# wificontrolpanel.net
KiCad netlist of a schematic drawn in EAGLE
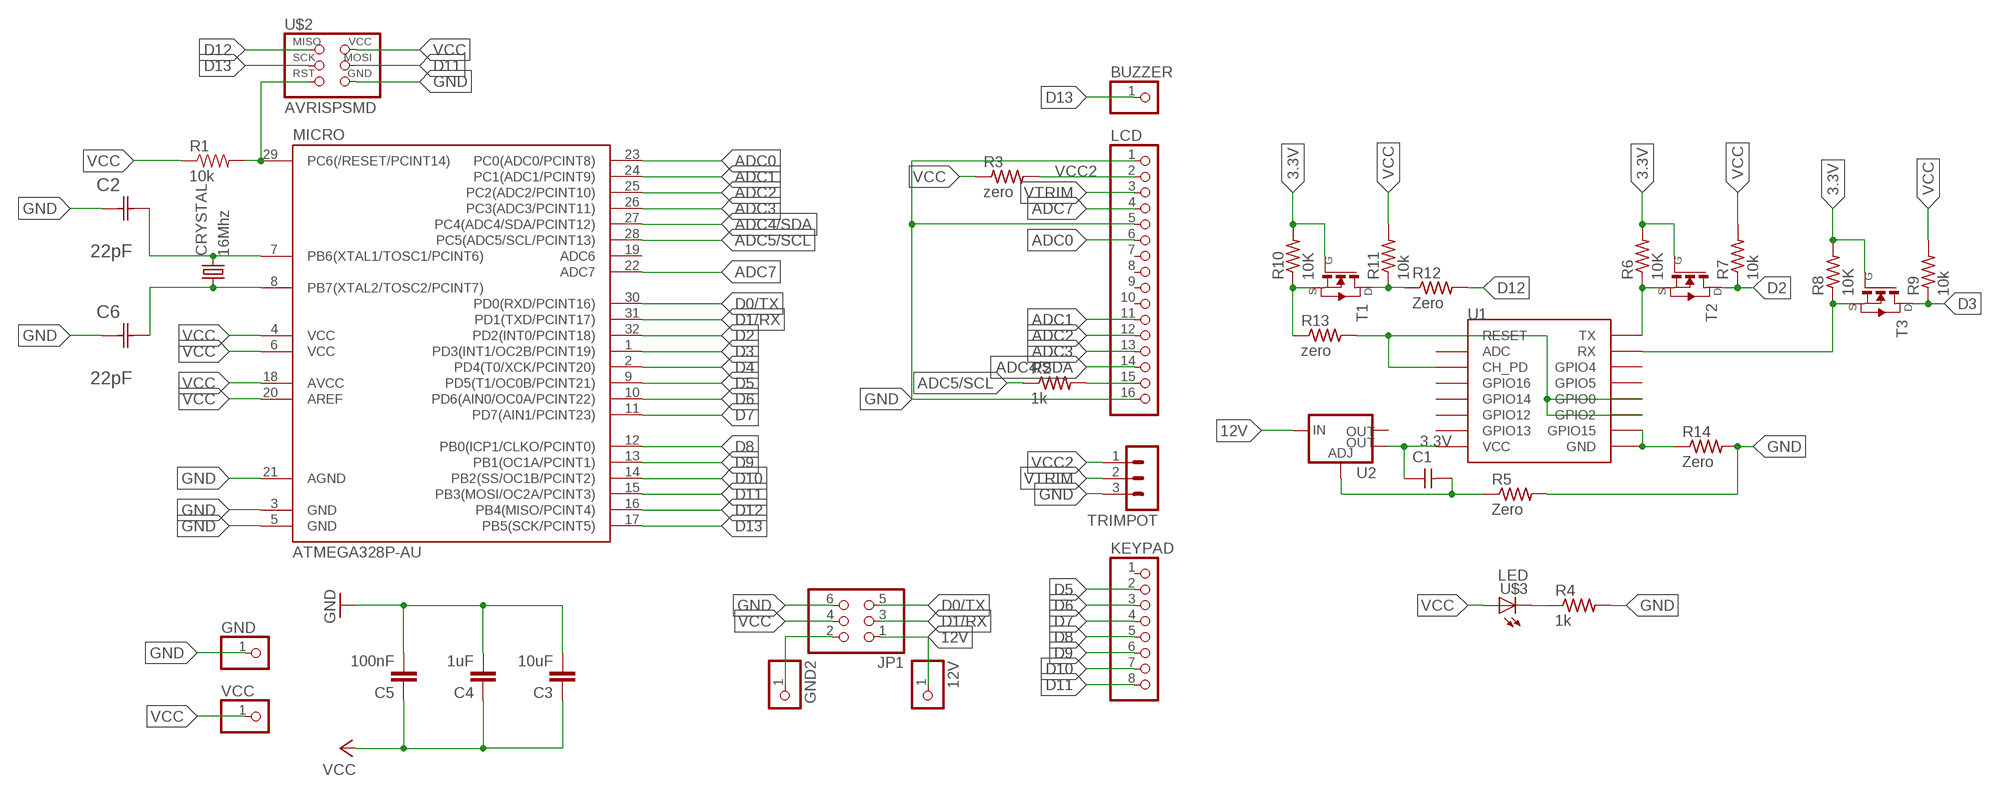
[diagram p0: schematic, sheet 1]

(export (version "E")
  (design (tool "Eeschema 10.0.6"))
  (components
    (comp (ref "12V")
      (value "PINHD-1X1")
      (footprint "eagle-import:1X01")
      (libsource (lib "eagle-import") (part "PINHD-1X1"))
    )
    (comp (ref "BUZZER")
      (value "PINHD-1X1")
      (footprint "eagle-import:1X01")
      (libsource (lib "eagle-import") (part "PINHD-1X1"))
    )
    (comp (ref "C1")
      (value "CAP-UNPOLARIZEDFAB")
      (footprint "eagle-import:C1206FAB")
      (libsource (lib "eagle-import") (part "CAP-UNPOLARIZEDFAB"))
    )
    (comp (ref "C2")
      (value "22pF")
      (footprint "eagle-import:CAPC3216X178N")
      (fields (field (name "MPN") "0612ZC225MAT2A") (field (name "TOLERANCE") "±20%"))
      (libsource (lib "eagle-import") (part "0612ZC225MAT2A"))
    )
    (comp (ref "C3")
      (value "10uF")
      (footprint "eagle-import:1206")
      (libsource (lib "eagle-import") (part "CAP1206"))
    )
    (comp (ref "C4")
      (value "1uF")
      (footprint "eagle-import:1206")
      (libsource (lib "eagle-import") (part "CAP1206"))
    )
    (comp (ref "C5")
      (value "100nF")
      (footprint "eagle-import:1206")
      (libsource (lib "eagle-import") (part "CAP1206"))
    )
    (comp (ref "C6")
      (value "22pF")
      (footprint "eagle-import:CAPC3216X178N")
      (fields (field (name "MPN") "0612ZC225MAT2A") (field (name "TOLERANCE") "±20%"))
      (libsource (lib "eagle-import") (part "0612ZC225MAT2A"))
    )
    (comp (ref "CRYSTAL")
      (value "16Mhz")
      (footprint "eagle-import:CSM-7X-DU")
      (libsource (lib "eagle-import") (part "CSM-7X-DU"))
    )
    (comp (ref "GND")
      (value "PINHD-1X1")
      (footprint "eagle-import:1X01")
      (libsource (lib "eagle-import") (part "PINHD-1X1"))
    )
    (comp (ref "GND2")
      (value "PINHD-1X1")
      (footprint "eagle-import:1X01")
      (libsource (lib "eagle-import") (part "PINHD-1X1"))
    )
    (comp (ref "JP1")
      (value "PINHD-2X3-SMD")
      (footprint "eagle-import:2X03SMD")
      (libsource (lib "eagle-import") (part "PINHD-2X3-SMD"))
    )
    (comp (ref "KEYPAD")
      (value "PINHD-1X8")
      (footprint "eagle-import:1X08")
      (libsource (lib "eagle-import") (part "PINHD-1X8"))
    )
    (comp (ref "LCD")
      (value "PINHD-1X16")
      (footprint "eagle-import:1X16")
      (libsource (lib "eagle-import") (part "PINHD-1X16"))
    )
    (comp (ref "MICRO")
      (value "ATMEGA328P-AU")
      (footprint "eagle-import:TQFP32-08")
      (libsource (lib "eagle-import") (part "ATMEGA48/88/168-AU"))
    )
    (comp (ref "R1")
      (value "10k")
      (footprint "eagle-import:1206")
      (libsource (lib "eagle-import") (part "RESISTOR1206"))
    )
    (comp (ref "R2")
      (value "1k")
      (footprint "eagle-import:R1206FAB")
      (libsource (lib "eagle-import") (part "RES-US1206FAB"))
    )
    (comp (ref "R3")
      (value "zero")
      (footprint "eagle-import:R1206FAB")
      (libsource (lib "eagle-import") (part "RES-US1206FAB"))
    )
    (comp (ref "R4")
      (value "1k")
      (footprint "eagle-import:R1206")
      (libsource (lib "eagle-import") (part "RES-US1206"))
    )
    (comp (ref "R5")
      (value "Zero")
      (footprint "eagle-import:R1206FAB")
      (libsource (lib "eagle-import") (part "RES-US1206FAB"))
    )
    (comp (ref "R6")
      (value "10K")
      (footprint "eagle-import:R1206FAB")
      (libsource (lib "eagle-import") (part "RES-US1206FAB"))
    )
    (comp (ref "R7")
      (value "10k")
      (footprint "eagle-import:R1206FAB")
      (libsource (lib "eagle-import") (part "RES-US1206FAB"))
    )
    (comp (ref "R8")
      (value "10K")
      (footprint "eagle-import:R1206FAB")
      (libsource (lib "eagle-import") (part "RES-US1206FAB"))
    )
    (comp (ref "R9")
      (value "10k")
      (footprint "eagle-import:R1206FAB")
      (libsource (lib "eagle-import") (part "RES-US1206FAB"))
    )
    (comp (ref "R10")
      (value "10K")
      (footprint "eagle-import:R1206FAB")
      (libsource (lib "eagle-import") (part "RES-US1206FAB"))
    )
    (comp (ref "R11")
      (value "10k")
      (footprint "eagle-import:R1206FAB")
      (libsource (lib "eagle-import") (part "RES-US1206FAB"))
    )
    (comp (ref "R12")
      (value "Zero")
      (footprint "eagle-import:R1206FAB")
      (libsource (lib "eagle-import") (part "RES-US1206FAB"))
    )
    (comp (ref "R13")
      (value "zero")
      (footprint "eagle-import:R1206FAB")
      (libsource (lib "eagle-import") (part "RES-US1206FAB"))
    )
    (comp (ref "R14")
      (value "Zero")
      (footprint "eagle-import:R1206FAB")
      (libsource (lib "eagle-import") (part "RES-US1206FAB"))
    )
    (comp (ref "T1")
      (value "NMOSFETSOT23")
      (footprint "eagle-import:SOT-23")
      (libsource (lib "eagle-import") (part "NMOSFETSOT23"))
    )
    (comp (ref "T2")
      (value "NMOSFETSOT23")
      (footprint "eagle-import:SOT-23")
      (libsource (lib "eagle-import") (part "NMOSFETSOT23"))
    )
    (comp (ref "T3")
      (value "NMOSFETSOT23")
      (footprint "eagle-import:SOT-23")
      (libsource (lib "eagle-import") (part "NMOSFETSOT23"))
    )
    (comp (ref "TRIMPOT")
      (value "MA03-1")
      (footprint "eagle-import:MA03-1")
      (libsource (lib "eagle-import") (part "MA03-1"))
    )
    (comp (ref "U$2")
      (value "AVRISPSMD")
      (footprint "eagle-import:2X03SMD")
      (libsource (lib "eagle-import") (part "AVRISPSMD"))
    )
    (comp (ref "U$3")
      (value "LED")
      (footprint "eagle-import:LED1206")
      (libsource (lib "eagle-import") (part "LED"))
    )
    (comp (ref "U1")
      (value "ESP12SMD")
      (footprint "eagle-import:ESP12-SMD")
      (libsource (lib "eagle-import") (part "ESP12SMD"))
    )
    (comp (ref "U2")
      (value "V_REG_LM1117SOT223")
      (footprint "eagle-import:SOT223")
      (libsource (lib "eagle-import") (part "V_REG_LM1117SOT223"))
    )
    (comp (ref "VCC")
      (value "PINHD-1X1")
      (footprint "eagle-import:1X01")
      (libsource (lib "eagle-import") (part "PINHD-1X1"))
    )
  )
  (nets
    (net (code "1") (name "3.3V") (class "Default")
      (node (ref "C1") (pin "1") (pinfunction "1_1") (pintype "passive"))
      (node (ref "R10") (pin "2") (pinfunction "2_2") (pintype "passive"))
      (node (ref "R6") (pin "2") (pinfunction "2_2") (pintype "passive"))
      (node (ref "R8") (pin "2") (pinfunction "2_2") (pintype "passive"))
      (node (ref "T1") (pin "3") (pinfunction "G_3") (pintype "passive"))
      (node (ref "T2") (pin "3") (pinfunction "G_3") (pintype "passive"))
      (node (ref "T3") (pin "3") (pinfunction "G_3") (pintype "passive"))
      (node (ref "U1") (pin "VCC") (pinfunction "VCC_VCC") (pintype "bidirectional"))
      (node (ref "U2") (pin "4") (pinfunction "OUT_4") (pintype "output"))
    )
    (net (code "2") (name "12V") (class "Default")
      (node (ref "12V") (pin "1") (pinfunction "1_1") (pintype "passive"))
      (node (ref "JP1") (pin "1") (pinfunction "1_1") (pintype "passive"))
      (node (ref "U2") (pin "3") (pinfunction "IN_3") (pintype "input"))
    )
    (net (code "3") (name "ADC0") (class "Default")
      (node (ref "LCD") (pin "6") (pinfunction "6_6") (pintype "passive"))
      (node (ref "MICRO") (pin "23") (pinfunction "PC0(ADC0/PCINT8)_23") (pintype "bidirectional"))
    )
    (net (code "4") (name "ADC1") (class "Default")
      (node (ref "LCD") (pin "11") (pinfunction "11_11") (pintype "passive"))
      (node (ref "MICRO") (pin "24") (pinfunction "PC1(ADC1/PCINT9)_24") (pintype "bidirectional"))
    )
    (net (code "5") (name "ADC2") (class "Default")
      (node (ref "LCD") (pin "12") (pinfunction "12_12") (pintype "passive"))
      (node (ref "MICRO") (pin "25") (pinfunction "PC2(ADC2/PCINT10)_25") (pintype "bidirectional"))
    )
    (net (code "6") (name "ADC3") (class "Default")
      (node (ref "LCD") (pin "13") (pinfunction "13_13") (pintype "passive"))
      (node (ref "MICRO") (pin "26") (pinfunction "PC3(ADC3/PCINT11)_26") (pintype "bidirectional"))
    )
    (net (code "7") (name "ADC4{slash}SDA") (class "Default")
      (node (ref "LCD") (pin "14") (pinfunction "14_14") (pintype "passive"))
      (node (ref "MICRO") (pin "27") (pinfunction "PC4(ADC4/SDA/PCINT12)_27") (pintype "bidirectional"))
    )
    (net (code "8") (name "ADC5{slash}SCL") (class "Default")
      (node (ref "MICRO") (pin "28") (pinfunction "PC5(ADC5/SCL/PCINT13)_28") (pintype "bidirectional"))
      (node (ref "R2") (pin "1") (pinfunction "1_1") (pintype "passive"))
    )
    (net (code "9") (name "ADC7") (class "Default")
      (node (ref "LCD") (pin "4") (pinfunction "4_4") (pintype "passive"))
      (node (ref "MICRO") (pin "22") (pinfunction "ADC7_22") (pintype "passive"))
    )
    (net (code "10") (name "D0{slash}TX") (class "Default")
      (node (ref "JP1") (pin "5") (pinfunction "5_5") (pintype "passive"))
      (node (ref "MICRO") (pin "30") (pinfunction "PD0(RXD/PCINT16)_30") (pintype "bidirectional"))
    )
    (net (code "11") (name "D1{slash}RX") (class "Default")
      (node (ref "JP1") (pin "3") (pinfunction "3_3") (pintype "passive"))
      (node (ref "MICRO") (pin "31") (pinfunction "PD1(TXD/PCINT17)_31") (pintype "bidirectional"))
    )
    (net (code "12") (name "D2") (class "Default")
      (node (ref "MICRO") (pin "32") (pinfunction "PD2(INT0/PCINT18)_32") (pintype "bidirectional"))
      (node (ref "R7") (pin "1") (pinfunction "1_1") (pintype "passive"))
      (node (ref "T2") (pin "1") (pinfunction "D_1") (pintype "passive"))
    )
    (net (code "13") (name "D3") (class "Default")
      (node (ref "MICRO") (pin "1") (pinfunction "PD3(INT1/OC2B/PCINT19)_1") (pintype "bidirectional"))
      (node (ref "R9") (pin "1") (pinfunction "1_1") (pintype "passive"))
      (node (ref "T3") (pin "1") (pinfunction "D_1") (pintype "passive"))
    )
    (net (code "14") (name "D4") (class "Default")
      (node (ref "MICRO") (pin "2") (pinfunction "PD4(T0/XCK/PCINT20)_2") (pintype "bidirectional"))
    )
    (net (code "15") (name "D5") (class "Default")
      (node (ref "KEYPAD") (pin "2") (pinfunction "2_2") (pintype "passive"))
      (node (ref "MICRO") (pin "9") (pinfunction "PD5(T1/OC0B/PCINT21)_9") (pintype "bidirectional"))
    )
    (net (code "16") (name "D6") (class "Default")
      (node (ref "KEYPAD") (pin "3") (pinfunction "3_3") (pintype "passive"))
      (node (ref "MICRO") (pin "10") (pinfunction "PD6(AIN0/OC0A/PCINT22)_10") (pintype "bidirectional"))
    )
    (net (code "17") (name "D7") (class "Default")
      (node (ref "KEYPAD") (pin "4") (pinfunction "4_4") (pintype "passive"))
      (node (ref "MICRO") (pin "11") (pinfunction "PD7(AIN1/PCINT23)_11") (pintype "bidirectional"))
    )
    (net (code "18") (name "D8") (class "Default")
      (node (ref "KEYPAD") (pin "5") (pinfunction "5_5") (pintype "passive"))
      (node (ref "MICRO") (pin "12") (pinfunction "PB0(ICP1/CLKO/PCINT0)_12") (pintype "bidirectional"))
    )
    (net (code "19") (name "D9") (class "Default")
      (node (ref "KEYPAD") (pin "6") (pinfunction "6_6") (pintype "passive"))
      (node (ref "MICRO") (pin "13") (pinfunction "PB1(OC1A/PCINT1)_13") (pintype "bidirectional"))
    )
    (net (code "20") (name "D10") (class "Default")
      (node (ref "KEYPAD") (pin "7") (pinfunction "7_7") (pintype "passive"))
      (node (ref "MICRO") (pin "14") (pinfunction "PB2(SS/OC1B/PCINT2)_14") (pintype "bidirectional"))
    )
    (net (code "21") (name "D11") (class "Default")
      (node (ref "KEYPAD") (pin "8") (pinfunction "8_8") (pintype "passive"))
      (node (ref "MICRO") (pin "15") (pinfunction "PB3(MOSI/OC2A/PCINT3)_15") (pintype "bidirectional"))
      (node (ref "U$2") (pin "4") (pinfunction "MOSI_4") (pintype "passive"))
    )
    (net (code "22") (name "D12") (class "Default")
      (node (ref "MICRO") (pin "16") (pinfunction "PB4(MISO/PCINT4)_16") (pintype "bidirectional"))
      (node (ref "R12") (pin "2") (pinfunction "2_2") (pintype "passive"))
      (node (ref "U$2") (pin "1") (pinfunction "MISO_1") (pintype "passive"))
    )
    (net (code "23") (name "D13") (class "Default")
      (node (ref "BUZZER") (pin "1") (pinfunction "1_1") (pintype "passive"))
      (node (ref "MICRO") (pin "17") (pinfunction "PB5(SCK/PCINT5)_17") (pintype "bidirectional"))
      (node (ref "U$2") (pin "3") (pinfunction "SCK_3") (pintype "passive"))
    )
    (net (code "24") (name "GND") (class "Default")
      (node (ref "C2") (pin "1") (pinfunction "C1_1") (pintype "passive"))
      (node (ref "C3") (pin "2") (pinfunction "2_2") (pintype "passive"))
      (node (ref "C4") (pin "2") (pinfunction "2_2") (pintype "passive"))
      (node (ref "C5") (pin "2") (pinfunction "2_2") (pintype "passive"))
      (node (ref "C6") (pin "1") (pinfunction "C1_1") (pintype "passive"))
      (node (ref "GND") (pin "1") (pinfunction "1_1") (pintype "passive"))
      (node (ref "JP1") (pin "6") (pinfunction "6_6") (pintype "passive"))
      (node (ref "LCD") (pin "1") (pinfunction "1_1") (pintype "passive"))
      (node (ref "LCD") (pin "16") (pinfunction "16_16") (pintype "passive"))
      (node (ref "LCD") (pin "5") (pinfunction "5_5") (pintype "passive"))
      (node (ref "MICRO") (pin "21") (pinfunction "AGND_21") (pintype "power_in"))
      (node (ref "MICRO") (pin "3") (pinfunction "GND_3") (pintype "power_in"))
      (node (ref "MICRO") (pin "5") (pinfunction "GND_5") (pintype "power_in"))
      (node (ref "R14") (pin "2") (pinfunction "2_2") (pintype "passive"))
      (node (ref "R4") (pin "2") (pinfunction "2_2") (pintype "passive"))
      (node (ref "R5") (pin "2") (pinfunction "2_2") (pintype "passive"))
      (node (ref "TRIMPOT") (pin "3") (pinfunction "3_3") (pintype "passive"))
      (node (ref "U$2") (pin "6") (pinfunction "GND_6") (pintype "passive"))
    )
    (net (code "25") (name "Net-(C2-C2)") (class "Default")
      (node (ref "C2") (pin "2") (pinfunction "C2_2") (pintype "passive"))
      (node (ref "CRYSTAL") (pin "2") (pinfunction "2_2") (pintype "passive"))
      (node (ref "MICRO") (pin "7") (pinfunction "PB6(XTAL1/TOSC1/PCINT6)_7") (pintype "bidirectional"))
    )
    (net (code "26") (name "Net-(C6-C2)") (class "Default")
      (node (ref "C6") (pin "2") (pinfunction "C2_2") (pintype "passive"))
      (node (ref "CRYSTAL") (pin "1") (pinfunction "1_1") (pintype "passive"))
      (node (ref "MICRO") (pin "8") (pinfunction "PB7(XTAL2/TOSC2/PCINT7)_8") (pintype "bidirectional"))
    )
    (net (code "27") (name "Net-(GND2-Pad1)") (class "Default")
      (node (ref "GND2") (pin "1") (pinfunction "1_1") (pintype "passive"))
      (node (ref "JP1") (pin "2") (pinfunction "2_2") (pintype "passive"))
    )
    (net (code "28") (name "Net-(LCD-Pad15)") (class "Default")
      (node (ref "LCD") (pin "15") (pinfunction "15_15") (pintype "passive"))
      (node (ref "R2") (pin "2") (pinfunction "2_2") (pintype "passive"))
    )
    (net (code "29") (name "Net-(MICRO-PC6({slash}RESET{slash}PCINT14))") (class "Default")
      (node (ref "MICRO") (pin "29") (pinfunction "PC6(/RESET/PCINT14)_29") (pintype "bidirectional"))
      (node (ref "R1") (pin "2") (pinfunction "2_2") (pintype "passive"))
      (node (ref "U$2") (pin "5") (pinfunction "RST_5") (pintype "passive"))
    )
    (net (code "30") (name "Net-(R13-Pad2)") (class "Default")
      (node (ref "R13") (pin "2") (pinfunction "2_2") (pintype "passive"))
      (node (ref "U1") (pin "CH_PD") (pinfunction "CH_PD_CH_PD") (pintype "bidirectional"))
      (node (ref "U1") (pin "GPIO0") (pinfunction "GPIO0_GPIO0") (pintype "bidirectional"))
      (node (ref "U1") (pin "GPIO2") (pinfunction "GPIO2_GPIO2") (pintype "bidirectional"))
      (node (ref "U1") (pin "RESET") (pinfunction "RESET_RESET") (pintype "bidirectional"))
    )
    (net (code "31") (name "Net-(R14-Pad1)") (class "Default")
      (node (ref "R14") (pin "1") (pinfunction "1_1") (pintype "passive"))
      (node (ref "U1") (pin "GND") (pinfunction "GND_GND") (pintype "bidirectional"))
      (node (ref "U1") (pin "GPIO15") (pinfunction "GPIO15_GPIO15") (pintype "bidirectional"))
    )
    (net (code "32") (name "Net-(T1-D)") (class "Default")
      (node (ref "R11") (pin "1") (pinfunction "1_1") (pintype "passive"))
      (node (ref "R12") (pin "1") (pinfunction "1_1") (pintype "passive"))
      (node (ref "T1") (pin "1") (pinfunction "D_1") (pintype "passive"))
    )
    (net (code "33") (name "Net-(T1-S)") (class "Default")
      (node (ref "R10") (pin "1") (pinfunction "1_1") (pintype "passive"))
      (node (ref "R13") (pin "1") (pinfunction "1_1") (pintype "passive"))
      (node (ref "T1") (pin "2") (pinfunction "S_2") (pintype "passive"))
    )
    (net (code "34") (name "Net-(T2-S)") (class "Default")
      (node (ref "R6") (pin "1") (pinfunction "1_1") (pintype "passive"))
      (node (ref "T2") (pin "2") (pinfunction "S_2") (pintype "passive"))
      (node (ref "U1") (pin "TXD0") (pinfunction "TX_TXD0") (pintype "bidirectional"))
    )
    (net (code "35") (name "Net-(T3-S)") (class "Default")
      (node (ref "R8") (pin "1") (pinfunction "1_1") (pintype "passive"))
      (node (ref "T3") (pin "2") (pinfunction "S_2") (pintype "passive"))
      (node (ref "U1") (pin "RXD0") (pinfunction "RX_RXD0") (pintype "bidirectional"))
    )
    (net (code "36") (name "Net-(U$3-C)") (class "Default")
      (node (ref "R4") (pin "1") (pinfunction "1_1") (pintype "passive"))
      (node (ref "U$3") (pin "2") (pinfunction "C_2") (pintype "passive"))
    )
    (net (code "37") (name "Net-(U2-ADJ)") (class "Default")
      (node (ref "C1") (pin "2") (pinfunction "2_2") (pintype "passive"))
      (node (ref "R5") (pin "1") (pinfunction "1_1") (pintype "passive"))
      (node (ref "U2") (pin "1") (pinfunction "ADJ_1") (pintype "input"))
    )
    (net (code "38") (name "VCC") (class "Default")
      (node (ref "C3") (pin "1") (pinfunction "1_1") (pintype "passive"))
      (node (ref "C4") (pin "1") (pinfunction "1_1") (pintype "passive"))
      (node (ref "C5") (pin "1") (pinfunction "1_1") (pintype "passive"))
      (node (ref "JP1") (pin "4") (pinfunction "4_4") (pintype "passive"))
      (node (ref "MICRO") (pin "18") (pinfunction "AVCC_18") (pintype "passive"))
      (node (ref "MICRO") (pin "20") (pinfunction "AREF_20") (pintype "passive"))
      (node (ref "MICRO") (pin "4") (pinfunction "VCC_4") (pintype "power_in"))
      (node (ref "MICRO") (pin "6") (pinfunction "VCC_6") (pintype "power_in"))
      (node (ref "R1") (pin "1") (pinfunction "1_1") (pintype "passive"))
      (node (ref "R11") (pin "2") (pinfunction "2_2") (pintype "passive"))
      (node (ref "R3") (pin "1") (pinfunction "1_1") (pintype "passive"))
      (node (ref "R7") (pin "2") (pinfunction "2_2") (pintype "passive"))
      (node (ref "R9") (pin "2") (pinfunction "2_2") (pintype "passive"))
      (node (ref "U$2") (pin "2") (pinfunction "VCC_2") (pintype "passive"))
      (node (ref "U$3") (pin "1") (pinfunction "A_1") (pintype "passive"))
      (node (ref "VCC") (pin "1") (pinfunction "1_1") (pintype "passive"))
    )
    (net (code "39") (name "VCC2") (class "Default")
      (node (ref "LCD") (pin "2") (pinfunction "2_2") (pintype "passive"))
      (node (ref "R3") (pin "2") (pinfunction "2_2") (pintype "passive"))
      (node (ref "TRIMPOT") (pin "1") (pinfunction "1_1") (pintype "passive"))
    )
    (net (code "40") (name "VTRIM") (class "Default")
      (node (ref "LCD") (pin "3") (pinfunction "3_3") (pintype "passive"))
      (node (ref "TRIMPOT") (pin "2") (pinfunction "2_2") (pintype "passive"))
    )
    (net (code "41") (name "unconnected-(KEYPAD-Pad1)") (class "Default")
      (node (ref "KEYPAD") (pin "1") (pinfunction "1_1") (pintype "passive"))
    )
    (net (code "42") (name "unconnected-(LCD-Pad7)") (class "Default")
      (node (ref "LCD") (pin "7") (pinfunction "7_7") (pintype "passive"))
    )
    (net (code "43") (name "unconnected-(LCD-Pad8)") (class "Default")
      (node (ref "LCD") (pin "8") (pinfunction "8_8") (pintype "passive"))
    )
    (net (code "44") (name "unconnected-(LCD-Pad9)") (class "Default")
      (node (ref "LCD") (pin "9") (pinfunction "9_9") (pintype "passive"))
    )
    (net (code "45") (name "unconnected-(LCD-Pad10)") (class "Default")
      (node (ref "LCD") (pin "10") (pinfunction "10_10") (pintype "passive"))
    )
    (net (code "46") (name "unconnected-(MICRO-ADC6-Pad19)") (class "Default")
      (node (ref "MICRO") (pin "19") (pinfunction "ADC6_19") (pintype "passive"))
    )
    (net (code "47") (name "unconnected-(U1-PadADC)") (class "Default")
      (node (ref "U1") (pin "ADC") (pinfunction "ADC_ADC") (pintype "bidirectional"))
    )
    (net (code "48") (name "unconnected-(U1-PadGPIO4)") (class "Default")
      (node (ref "U1") (pin "GPIO4") (pinfunction "GPIO4_GPIO4") (pintype "bidirectional"))
    )
    (net (code "49") (name "unconnected-(U1-PadGPIO5)") (class "Default")
      (node (ref "U1") (pin "GPIO5") (pinfunction "GPIO5_GPIO5") (pintype "bidirectional"))
    )
    (net (code "50") (name "unconnected-(U1-PadGPIO12)") (class "Default")
      (node (ref "U1") (pin "GPIO12") (pinfunction "GPIO12_GPIO12") (pintype "bidirectional"))
    )
    (net (code "51") (name "unconnected-(U1-PadGPIO13)") (class "Default")
      (node (ref "U1") (pin "GPIO13") (pinfunction "GPIO13_GPIO13") (pintype "bidirectional"))
    )
    (net (code "52") (name "unconnected-(U1-PadGPIO14)") (class "Default")
      (node (ref "U1") (pin "GPIO14") (pinfunction "GPIO14_GPIO14") (pintype "bidirectional"))
    )
    (net (code "53") (name "unconnected-(U1-PadGPIO16)") (class "Default")
      (node (ref "U1") (pin "GPIO16") (pinfunction "GPIO16_GPIO16") (pintype "bidirectional"))
    )
    (net (code "54") (name "unconnected-(U2-OUT-Pad2)") (class "Default")
      (node (ref "U2") (pin "2") (pinfunction "OUT_2") (pintype "output"))
    )
  )
)
